# BQ76930.net
KiCad netlist of a schematic drawn in Altium Designer
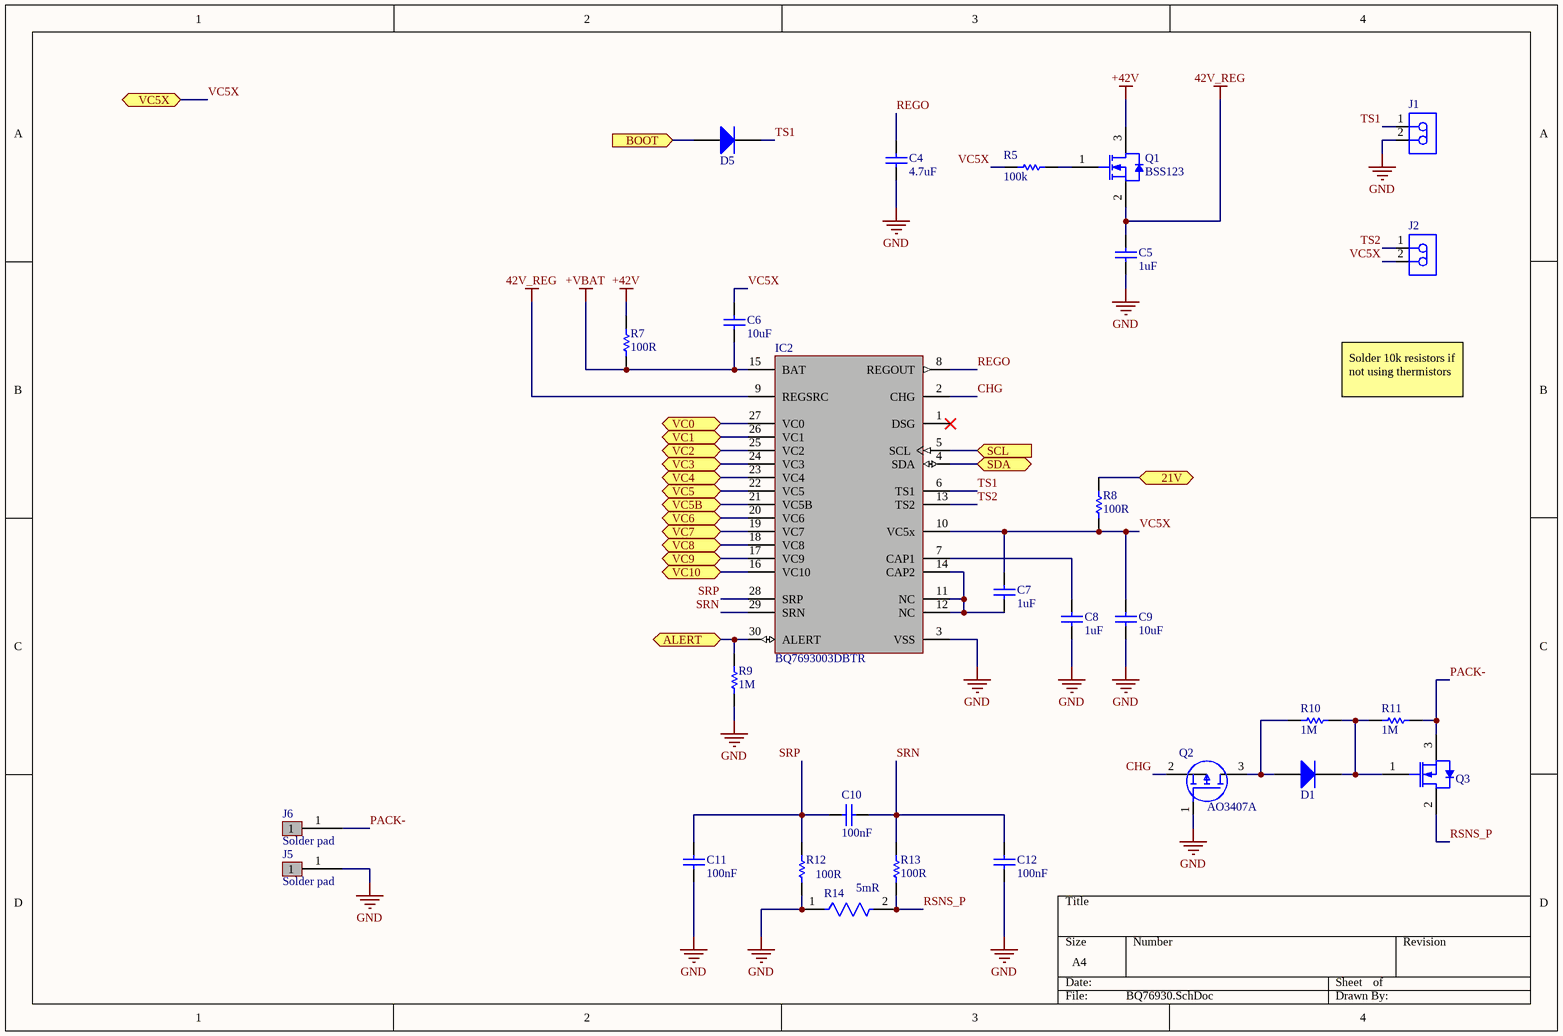
[diagram p0: BQ76930.SchDoc]

(export (version "E")
  (design (tool "Eeschema 10.0.6"))
  (components
    (comp (ref "C4")
      (value "4.7uF")
      (footprint "Wurth 0603 capacitor")
      (fields (field (name "Comment") "Generic Capacitor 4.7uF 0603"))
      (libsource (lib "Passives") (part "Generic Capacitor 4.7uF 0603"))
    )
    (comp (ref "C5")
      (value "1uF")
      (footprint "Wurth 0603 capacitor")
      (fields (field (name "Comment") "Generic Capacitor 1uF 0603"))
      (libsource (lib "Passives") (part "Generic Capacitor 1uF 0603"))
    )
    (comp (ref "C6")
      (value "10uF")
      (footprint "Wurth 0603 capacitor")
      (fields (field (name "Comment") "Generic Capacitor 10uF 0603"))
      (libsource (lib "Passives") (part "Generic Capacitor 10uF 0603"))
    )
    (comp (ref "C7")
      (value "1uF")
      (footprint "Wurth 0603 capacitor")
      (fields (field (name "Comment") "Generic Capacitor 1uF 0603"))
      (libsource (lib "Passives") (part "Generic Capacitor 1uF 0603"))
    )
    (comp (ref "C8")
      (value "1uF")
      (footprint "Wurth 0603 capacitor")
      (fields (field (name "Comment") "Generic Capacitor 1uF 0603"))
      (libsource (lib "Passives") (part "Generic Capacitor 1uF 0603"))
    )
    (comp (ref "C9")
      (value "10uF")
      (footprint "Wurth 0603 capacitor")
      (fields (field (name "Comment") "Generic Capacitor 10uF 0603"))
      (libsource (lib "Passives") (part "Generic Capacitor 10uF 0603"))
    )
    (comp (ref "C10")
      (value "100nF")
      (footprint "Wurth 0603 capacitor")
      (fields (field (name "Comment") "Generic Capacitor 100nF 0603"))
      (libsource (lib "Passives") (part "Generic Capacitor 100nF 0603"))
    )
    (comp (ref "C11")
      (value "100nF")
      (footprint "Wurth 0603 capacitor")
      (fields (field (name "Comment") "Generic Capacitor 100nF 0603"))
      (libsource (lib "Passives") (part "Generic Capacitor 100nF 0603"))
    )
    (comp (ref "C12")
      (value "100nF")
      (footprint "Wurth 0603 capacitor")
      (fields (field (name "Comment") "Generic Capacitor 100nF 0603"))
      (libsource (lib "Passives") (part "Generic Capacitor 100nF 0603"))
    )
    (comp (ref "D1")
      (value "1N4148W-7-F")
      (footprint "DIOD-SOD123-2_V")
      (description "Fast Switching Diode, 100 V, 0.15 A, -65 to 150 degC, 2-Pin?SOD123, RoHS, Tape and Reel")
      (fields (field (name "MANUFACTURER") "DiodesIncorporated"))
      (libsource (lib "Altium Content Vault") (part "D-AK-2"))
    )
    (comp (ref "D5")
      (value "1N4148W-7-F")
      (footprint "DIOD-SOD123-2_V")
      (description "Fast Switching Diode, 100 V, 0.15 A, -65 to 150 degC, 2-Pin?SOD123, RoHS, Tape and Reel")
      (fields (field (name "MANUFACTURER") "DiodesIncorporated"))
      (libsource (lib "Altium Content Vault") (part "D-AK-2"))
    )
    (comp (ref "IC2")
      (value "BQ7693003DBTR")
      (footprint "Leaded:Texas Instruments TSSOP-30 7.8X4.4MM")
      (description "Power Supply Support Circuit, Adjustable, 1 Channel, PDSO30")
      (fields
        (field (name "OCTOPART") "https://octopart.com/bq7693003dbtr-texas+instruments-34472212")
        (field (name "MANUFACTURER") "Texas Instruments")
      )
      (libsource (lib "Battery_management") (part "Texas instruments BQ7693003DBTR"))
    )
    (comp (ref "J1")
      (value "B2B-PH-K-S(LF)(SN)")
      (footprint "JST-B2B-PH-K-S_V")
      (fields (field (name "MANUFACTURER") "JST"))
      (libsource (lib "Altium Content Vault") (part "CN-2P-F-QF2"))
    )
    (comp (ref "J2")
      (value "B2B-PH-K-S(LF)(SN)")
      (footprint "JST-B2B-PH-K-S_V")
      (fields (field (name "MANUFACTURER") "JST"))
      (libsource (lib "Altium Content Vault") (part "CN-2P-F-QF2"))
    )
    (comp (ref "J5")
      (value "Solder pad")
      (footprint "Leadless:Solder Pad 4X5MM")
      (libsource (lib "Connectors") (part "Solder pad"))
    )
    (comp (ref "J6")
      (value "Solder pad")
      (footprint "Leadless:Solder Pad 4X5MM")
      (libsource (lib "Connectors") (part "Solder pad"))
    )
    (comp (ref "Q1")
      (value "BSS123")
      (footprint "FAIR-SOT23-3_V")
      (fields (field (name "MANUFACTURER") "Fairchild"))
      (libsource (lib "Altium Content Vault") (part "NEMOS-GSD-3"))
    )
    (comp (ref "Q2")
      (value "AO3407A")
      (footprint "UMW SOT23-3")
      (description "MOSFET (P-Channel)")
      (libsource (lib "P CHN FET") (part "UMW AO3407A"))
    )
    (comp (ref "Q3")
      (value "MDT18N20")
      (footprint "Leaded:Minos TO-252-2L 6.3X9.6MM")
      (description "VDS = 200V,ID = 18A, VGS=30V")
      (libsource (lib "N CHN FET") (part "Minos MDT18N20"))
    )
    (comp (ref "R5")
      (value "100k")
      (footprint "Wurth 0603 Resistor")
      (fields (field (name "Comment") "CRCW060310K0FKEA"))
      (libsource (lib "Passives") (part "Generic Resistor 100k 0603"))
    )
    (comp (ref "R7")
      (value "100R")
      (footprint "Wurth 0603 Resistor")
      (fields (field (name "Comment") "Generic Resistor 100R 0603"))
      (libsource (lib "Passives") (part "Generic Resistor 100R 0603"))
    )
    (comp (ref "R8")
      (value "100R")
      (footprint "Wurth 0603 Resistor")
      (fields (field (name "Comment") "Generic Resistor 100R 0603"))
      (libsource (lib "Passives") (part "Generic Resistor 100R 0603"))
    )
    (comp (ref "R9")
      (value "1M")
      (footprint "Wurth 0603 Resistor")
      (fields (field (name "Comment") "Generic Resistor 1M 0603"))
      (libsource (lib "Passives") (part "Generic Resistor 1M 0603"))
    )
    (comp (ref "R10")
      (value "1M")
      (footprint "Wurth 0603 Resistor")
      (fields (field (name "Comment") "Generic Resistor 1M 0603"))
      (libsource (lib "Passives") (part "Generic Resistor 1M 0603"))
    )
    (comp (ref "R11")
      (value "1M")
      (footprint "Wurth 0603 Resistor")
      (fields (field (name "Comment") "Generic Resistor 1M 0603"))
      (libsource (lib "Passives") (part "Generic Resistor 1M 0603"))
    )
    (comp (ref "R12")
      (value "100R")
      (footprint "Wurth 0603 Resistor")
      (fields (field (name "Comment") "Generic Resistor 100R 0603"))
      (libsource (lib "Passives") (part "Generic Resistor 100R 0603"))
    )
    (comp (ref "R13")
      (value "100R")
      (footprint "Wurth 0603 Resistor")
      (fields (field (name "Comment") "Generic Resistor 100R 0603"))
      (libsource (lib "Passives") (part "Generic Resistor 100R 0603"))
    )
    (comp (ref "R14")
      (value "ERJ-M1WSF5M0U")
      (footprint "FP-ERJM1WS-MFG")
      (description "RES 0.005 OHM 1% 1W 2512")
      (fields (field (name "RESISTANCE") "5mR") (field (name "TOLERANCE") "1%"))
      (libsource (lib "Altium Content Vault") (part "8db39607336c341a927600551d01821"))
    )
  )
  (nets
    (net (code "1") (name "+42V") (class "Default")
      (node (ref "Q1") (pin "3") (pinfunction "D_3") (pintype "passive"))
      (node (ref "R7") (pin "1") (pinfunction "1_1") (pintype "passive"))
    )
    (net (code "2") (name "+VBAT") (class "Default")
      (node (ref "C6") (pin "1") (pinfunction "1_1") (pintype "passive"))
      (node (ref "IC2") (pin "15") (pinfunction "BAT_15") (pintype "power_in"))
      (node (ref "R7") (pin "2") (pinfunction "2_2") (pintype "passive"))
    )
    (net (code "3") (name "/21V") (class "Default")
      (node (ref "R8") (pin "2") (pinfunction "2_2") (pintype "passive"))
    )
    (net (code "4") (name "/ALERT") (class "Default")
      (node (ref "IC2") (pin "30") (pinfunction "ALERT_30") (pintype "bidirectional"))
      (node (ref "R9") (pin "2") (pinfunction "2_2") (pintype "passive"))
    )
    (net (code "5") (name "/BOOT") (class "Default")
      (node (ref "D5") (pin "1") (pinfunction "A_1") (pintype "passive"))
    )
    (net (code "6") (name "/CHG") (class "Default")
      (node (ref "IC2") (pin "2") (pinfunction "CHG_2") (pintype "passive"))
      (node (ref "Q2") (pin "2") (pinfunction "S_2") (pintype "passive"))
    )
    (net (code "7") (name "/PACK-") (class "Default")
      (node (ref "J6") (pin "1") (pinfunction "1_1") (pintype "passive"))
      (node (ref "Q3") (pin "3") (pinfunction "S_3") (pintype "passive"))
      (node (ref "R11") (pin "2") (pinfunction "2_2") (pintype "passive"))
    )
    (net (code "8") (name "/REGO") (class "Default")
      (node (ref "C4") (pin "2") (pinfunction "2_2") (pintype "passive"))
      (node (ref "IC2") (pin "8") (pinfunction "REGOUT_8") (pintype "output"))
    )
    (net (code "9") (name "/RSNS_P") (class "Default")
      (node (ref "Q3") (pin "2") (pinfunction "D_2") (pintype "passive"))
      (node (ref "R13") (pin "1") (pinfunction "1_1") (pintype "passive"))
      (node (ref "R14") (pin "2") (pinfunction "2_2") (pintype "passive"))
    )
    (net (code "10") (name "/SCL") (class "Default")
      (node (ref "IC2") (pin "5") (pinfunction "SCL_5") (pintype "input"))
    )
    (net (code "11") (name "/SDA") (class "Default")
      (node (ref "IC2") (pin "4") (pinfunction "SDA_4") (pintype "bidirectional"))
    )
    (net (code "12") (name "/SRN") (class "Default")
      (node (ref "C10") (pin "2") (pinfunction "2_2") (pintype "passive"))
      (node (ref "C12") (pin "2") (pinfunction "2_2") (pintype "passive"))
      (node (ref "IC2") (pin "29") (pinfunction "SRN_29") (pintype "passive"))
      (node (ref "R13") (pin "2") (pinfunction "2_2") (pintype "passive"))
    )
    (net (code "13") (name "/SRP") (class "Default")
      (node (ref "C10") (pin "1") (pinfunction "1_1") (pintype "passive"))
      (node (ref "C11") (pin "2") (pinfunction "2_2") (pintype "passive"))
      (node (ref "IC2") (pin "28") (pinfunction "SRP_28") (pintype "passive"))
      (node (ref "R12") (pin "2") (pinfunction "2_2") (pintype "passive"))
    )
    (net (code "14") (name "/TS1") (class "Default")
      (node (ref "D5") (pin "2") (pinfunction "K_2") (pintype "passive"))
      (node (ref "IC2") (pin "6") (pinfunction "TS1_6") (pintype "passive"))
      (node (ref "J1") (pin "1") (pinfunction "1_1") (pintype "passive"))
    )
    (net (code "15") (name "/TS2") (class "Default")
      (node (ref "IC2") (pin "13") (pinfunction "TS2_13") (pintype "passive"))
      (node (ref "J2") (pin "1") (pinfunction "1_1") (pintype "passive"))
    )
    (net (code "16") (name "/VC0") (class "Default")
      (node (ref "IC2") (pin "27") (pinfunction "VC0_27") (pintype "passive"))
    )
    (net (code "17") (name "/VC1") (class "Default")
      (node (ref "IC2") (pin "26") (pinfunction "VC1_26") (pintype "passive"))
    )
    (net (code "18") (name "/VC2") (class "Default")
      (node (ref "IC2") (pin "25") (pinfunction "VC2_25") (pintype "passive"))
    )
    (net (code "19") (name "/VC3") (class "Default")
      (node (ref "IC2") (pin "24") (pinfunction "VC3_24") (pintype "passive"))
    )
    (net (code "20") (name "/VC4") (class "Default")
      (node (ref "IC2") (pin "23") (pinfunction "VC4_23") (pintype "passive"))
    )
    (net (code "21") (name "/VC5") (class "Default")
      (node (ref "IC2") (pin "22") (pinfunction "VC5_22") (pintype "passive"))
    )
    (net (code "22") (name "/VC5B") (class "Default")
      (node (ref "IC2") (pin "21") (pinfunction "VC5B_21") (pintype "passive"))
    )
    (net (code "23") (name "/VC5X") (class "Default")
      (node (ref "C6") (pin "2") (pinfunction "2_2") (pintype "passive"))
      (node (ref "C7") (pin "2") (pinfunction "2_2") (pintype "passive"))
      (node (ref "C9") (pin "2") (pinfunction "2_2") (pintype "passive"))
      (node (ref "IC2") (pin "10") (pinfunction "VC5x_10") (pintype "passive"))
      (node (ref "J2") (pin "2") (pinfunction "2_2") (pintype "passive"))
      (node (ref "R5") (pin "2") (pinfunction "2_2") (pintype "passive"))
      (node (ref "R8") (pin "1") (pinfunction "1_1") (pintype "passive"))
    )
    (net (code "24") (name "/VC6") (class "Default")
      (node (ref "IC2") (pin "20") (pinfunction "VC6_20") (pintype "passive"))
    )
    (net (code "25") (name "/VC7") (class "Default")
      (node (ref "IC2") (pin "19") (pinfunction "VC7_19") (pintype "passive"))
    )
    (net (code "26") (name "/VC8") (class "Default")
      (node (ref "IC2") (pin "18") (pinfunction "VC8_18") (pintype "passive"))
    )
    (net (code "27") (name "/VC9") (class "Default")
      (node (ref "IC2") (pin "17") (pinfunction "VC9_17") (pintype "passive"))
    )
    (net (code "28") (name "/VC10") (class "Default")
      (node (ref "IC2") (pin "16") (pinfunction "VC10_16") (pintype "passive"))
    )
    (net (code "29") (name "42V_REG") (class "Default")
      (node (ref "C5") (pin "2") (pinfunction "2_2") (pintype "passive"))
      (node (ref "IC2") (pin "9") (pinfunction "REGSRC_9") (pintype "power_in"))
      (node (ref "Q1") (pin "2") (pinfunction "S_2") (pintype "passive"))
    )
    (net (code "30") (name "GND") (class "Default")
      (node (ref "C11") (pin "1") (pinfunction "1_1") (pintype "passive"))
      (node (ref "C12") (pin "1") (pinfunction "1_1") (pintype "passive"))
      (node (ref "C4") (pin "1") (pinfunction "1_1") (pintype "passive"))
      (node (ref "C5") (pin "1") (pinfunction "1_1") (pintype "passive"))
      (node (ref "C8") (pin "1") (pinfunction "1_1") (pintype "passive"))
      (node (ref "C9") (pin "1") (pinfunction "1_1") (pintype "passive"))
      (node (ref "IC2") (pin "3") (pinfunction "VSS_3") (pintype "power_in"))
      (node (ref "J1") (pin "2") (pinfunction "2_2") (pintype "passive"))
      (node (ref "J5") (pin "1") (pinfunction "1_1") (pintype "passive"))
      (node (ref "Q2") (pin "1") (pinfunction "G_1") (pintype "passive"))
      (node (ref "R12") (pin "1") (pinfunction "1_1") (pintype "passive"))
      (node (ref "R14") (pin "1") (pinfunction "1_1") (pintype "passive"))
      (node (ref "R9") (pin "1") (pinfunction "1_1") (pintype "passive"))
    )
    (net (code "31") (name "Net-(D1-A)") (class "Default")
      (node (ref "D1") (pin "1") (pinfunction "A_1") (pintype "passive"))
      (node (ref "Q2") (pin "3") (pinfunction "D_3") (pintype "passive"))
      (node (ref "R10") (pin "1") (pinfunction "1_1") (pintype "passive"))
    )
    (net (code "32") (name "Net-(D1-K)") (class "Default")
      (node (ref "D1") (pin "2") (pinfunction "K_2") (pintype "passive"))
      (node (ref "Q3") (pin "1") (pinfunction "G_1") (pintype "passive"))
      (node (ref "R10") (pin "2") (pinfunction "2_2") (pintype "passive"))
      (node (ref "R11") (pin "1") (pinfunction "1_1") (pintype "passive"))
    )
    (net (code "33") (name "Net-(IC2-CAP1)") (class "Default")
      (node (ref "C8") (pin "2") (pinfunction "2_2") (pintype "passive"))
      (node (ref "IC2") (pin "7") (pinfunction "CAP1_7") (pintype "passive"))
    )
    (net (code "34") (name "Net-(IC2-CAP2)") (class "Default")
      (node (ref "C7") (pin "1") (pinfunction "1_1") (pintype "passive"))
      (node (ref "IC2") (pin "11") (pinfunction "NC_11") (pintype "passive"))
      (node (ref "IC2") (pin "12") (pinfunction "NC_12") (pintype "passive"))
      (node (ref "IC2") (pin "14") (pinfunction "CAP2_14") (pintype "passive"))
    )
    (net (code "35") (name "Net-(Q1-G)") (class "Default")
      (node (ref "Q1") (pin "1") (pinfunction "G_1") (pintype "passive"))
      (node (ref "R5") (pin "1") (pinfunction "1_1") (pintype "passive"))
    )
    (net (code "36") (name "unconnected-(IC2-DSG-Pad1)") (class "Default")
      (node (ref "IC2") (pin "1") (pinfunction "DSG_1") (pintype "passive+no_connect"))
    )
  )
)
